# RP2040_MCU.net
KiCad netlist of a schematic drawn in Altium Designer
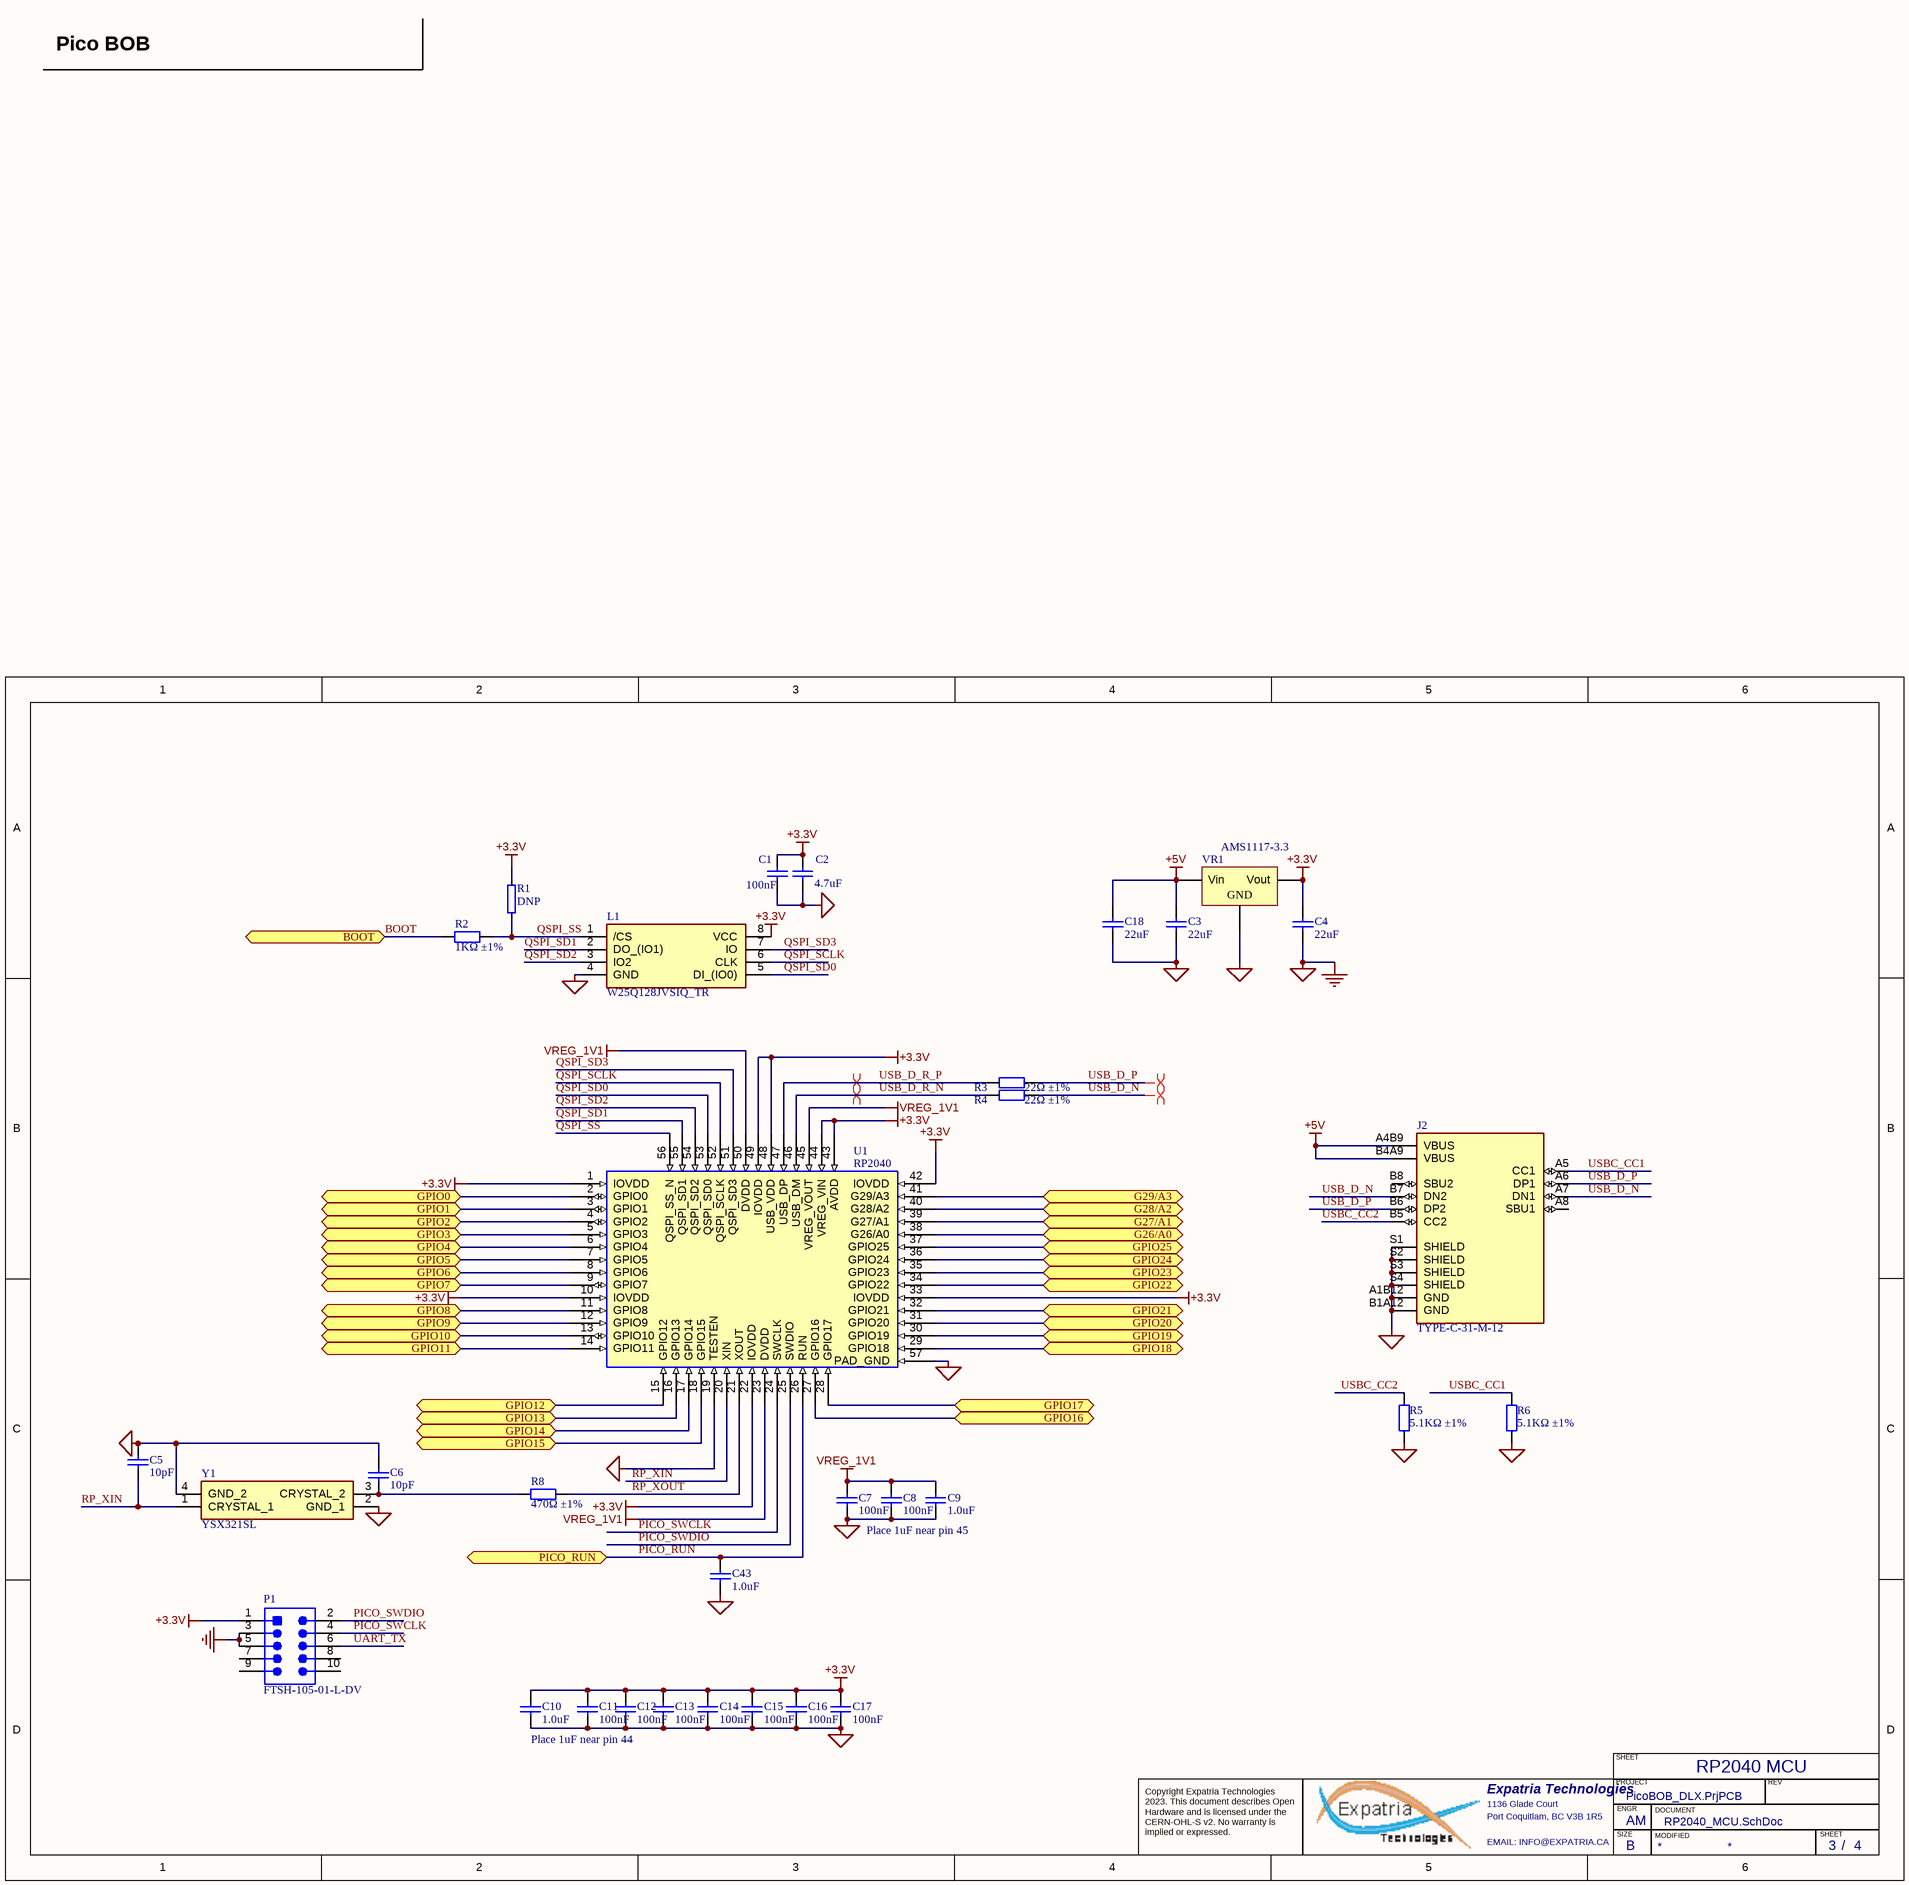
[diagram p0: RP2040_MCU.SchDoc]

(export (version "E")
  (design (tool "Eeschema 10.0.6"))
  (components
    (comp (ref "C1")
      (value "100nF")
      (footprint "0402_C")
      (description "Chip capacitors")
      (fields
        (field (name "MANUFACTURER") "Samsung Electro-Mechanics")
        (field (name "PARTNUMBER") "CL05B104KO5NNNC")
      )
      (libsource (lib "Cap") (part "0402 100nF (104) 10% 16V"))
    )
    (comp (ref "C2")
      (value "4.7uF")
      (footprint "0402_C")
      (description "Chip capacitor")
      (fields
        (field (name "MANUFACTURER") "Samsung Electro-Mechanics")
        (field (name "PARTNUMBER") "CL05A475MP5NRNC")
      )
      (libsource (lib "Cap") (part "0402 4.7uF (475) 20% 10V"))
    )
    (comp (ref "C3")
      (value "22uF")
      (footprint "0805_C")
      (description "Chip capacitors")
      (fields
        (field (name "MANUFACTURER") "Samsung Electro-Mechanics")
        (field (name "PARTNUMBER") "CL21A226MAQNNNE")
      )
      (libsource (lib "Cap") (part "0805 22uF (226) 20% 25V"))
    )
    (comp (ref "C4")
      (value "22uF")
      (footprint "0805_C")
      (description "Chip capacitors")
      (fields
        (field (name "MANUFACTURER") "Samsung Electro-Mechanics")
        (field (name "PARTNUMBER") "CL21A226MAQNNNE")
      )
      (libsource (lib "Cap") (part "0805 22uF (226) 20% 25V"))
    )
    (comp (ref "C5")
      (value "10pF")
      (footprint "0402_C")
      (description "Chip capacitors")
      (fields
        (field (name "MANUFACTURER") "Samsung Electro-Mechanics")
        (field (name "PARTNUMBER") "CL05C100JB5NNNC")
      )
      (libsource (lib "Cap") (part "0402 10pF (100) 5% 50V"))
    )
    (comp (ref "C6")
      (value "10pF")
      (footprint "0402_C")
      (description "Chip capacitors")
      (fields
        (field (name "MANUFACTURER") "Samsung Electro-Mechanics")
        (field (name "PARTNUMBER") "CL05C100JB5NNNC")
      )
      (libsource (lib "Cap") (part "0402 10pF (100) 5% 50V"))
    )
    (comp (ref "C7")
      (value "100nF")
      (footprint "0402_C")
      (description "Chip capacitors")
      (fields
        (field (name "MANUFACTURER") "Samsung Electro-Mechanics")
        (field (name "PARTNUMBER") "CL05B104KO5NNNC")
      )
      (libsource (lib "Cap") (part "0402 100nF (104) 10% 16V"))
    )
    (comp (ref "C8")
      (value "100nF")
      (footprint "0402_C")
      (description "Chip capacitors")
      (fields
        (field (name "MANUFACTURER") "Samsung Electro-Mechanics")
        (field (name "PARTNUMBER") "CL05B104KO5NNNC")
      )
      (libsource (lib "Cap") (part "0402 100nF (104) 10% 16V"))
    )
    (comp (ref "C9")
      (value "1.0uF")
      (footprint "0402_C")
      (description "Chip capacitor")
      (fields
        (field (name "MANUFACTURER") "Samsung Electro-Mechanics")
        (field (name "PARTNUMBER") "CL05A105KA5NQNC")
      )
      (libsource (lib "Cap") (part "0402 1.0uF (105) 10% 25V"))
    )
    (comp (ref "C10")
      (value "1.0uF")
      (footprint "0402_C")
      (description "Chip capacitor")
      (fields
        (field (name "MANUFACTURER") "Samsung Electro-Mechanics")
        (field (name "PARTNUMBER") "CL05A105KA5NQNC")
      )
      (libsource (lib "Cap") (part "0402 1.0uF (105) 10% 25V"))
    )
    (comp (ref "C11")
      (value "100nF")
      (footprint "0402_C")
      (description "Chip capacitors")
      (fields
        (field (name "MANUFACTURER") "Samsung Electro-Mechanics")
        (field (name "PARTNUMBER") "CL05B104KO5NNNC")
      )
      (libsource (lib "Cap") (part "0402 100nF (104) 10% 16V"))
    )
    (comp (ref "C12")
      (value "100nF")
      (footprint "0402_C")
      (description "Chip capacitors")
      (fields
        (field (name "MANUFACTURER") "Samsung Electro-Mechanics")
        (field (name "PARTNUMBER") "CL05B104KO5NNNC")
      )
      (libsource (lib "Cap") (part "0402 100nF (104) 10% 16V"))
    )
    (comp (ref "C13")
      (value "100nF")
      (footprint "0402_C")
      (description "Chip capacitors")
      (fields
        (field (name "MANUFACTURER") "Samsung Electro-Mechanics")
        (field (name "PARTNUMBER") "CL05B104KO5NNNC")
      )
      (libsource (lib "Cap") (part "0402 100nF (104) 10% 16V"))
    )
    (comp (ref "C14")
      (value "100nF")
      (footprint "0402_C")
      (description "Chip capacitors")
      (fields
        (field (name "MANUFACTURER") "Samsung Electro-Mechanics")
        (field (name "PARTNUMBER") "CL05B104KO5NNNC")
      )
      (libsource (lib "Cap") (part "0402 100nF (104) 10% 16V"))
    )
    (comp (ref "C15")
      (value "100nF")
      (footprint "0402_C")
      (description "Chip capacitors")
      (fields
        (field (name "MANUFACTURER") "Samsung Electro-Mechanics")
        (field (name "PARTNUMBER") "CL05B104KO5NNNC")
      )
      (libsource (lib "Cap") (part "0402 100nF (104) 10% 16V"))
    )
    (comp (ref "C16")
      (value "100nF")
      (footprint "0402_C")
      (description "Chip capacitors")
      (fields
        (field (name "MANUFACTURER") "Samsung Electro-Mechanics")
        (field (name "PARTNUMBER") "CL05B104KO5NNNC")
      )
      (libsource (lib "Cap") (part "0402 100nF (104) 10% 16V"))
    )
    (comp (ref "C17")
      (value "100nF")
      (footprint "0402_C")
      (description "Chip capacitors")
      (fields
        (field (name "MANUFACTURER") "Samsung Electro-Mechanics")
        (field (name "PARTNUMBER") "CL05B104KO5NNNC")
      )
      (libsource (lib "Cap") (part "0402 100nF (104) 10% 16V"))
    )
    (comp (ref "C18")
      (value "22uF")
      (footprint "0805_C")
      (description "Chip capacitors")
      (fields
        (field (name "MANUFACTURER") "Samsung Electro-Mechanics")
        (field (name "PARTNUMBER") "CL21A226MAQNNNE")
      )
      (libsource (lib "Cap") (part "0805 22uF (226) 20% 25V"))
    )
    (comp (ref "C43")
      (value "1.0uF")
      (footprint "0402_C")
      (description "Chip capacitor")
      (fields
        (field (name "MANUFACTURER") "Samsung Electro-Mechanics")
        (field (name "PARTNUMBER") "CL05A105KA5NQNC")
      )
      (libsource (lib "Cap") (part "0402 1.0uF (105) 10% 25V"))
    )
    (comp (ref "J2")
      (value "TYPE-C-31-M-12")
      (footprint "HRO_TYPE-C-31-M-12")
      (description "USB Connectors 24 Receptacle 1 8.94*7.3mm RoHS")
      (fields (field (name "MF") "HRO Electronics Co., Ltd."))
      (libsource (lib "Universal_CNC_Breakout") (part "TYPE-C-31-M-12"))
    )
    (comp (ref "L1")
      (value "W25Q128JVSIQ_TR")
      (footprint "SamacSys:SOIC127P780X195-8N")
      (description "Inductor")
      (fields
        (field (name "MANUFACTURER_PART_NUMBER") "W25Q128JVSIQ TR")
        (field (name "MOUSER PART NUMBER") "454-W25Q128JVSIQTR")
      )
      (libsource (lib "*") (part "W25Q128JVSIQ_TR"))
    )
    (comp (ref "P1")
      (value "FTSH-105-01-L-DV")
      (footprint "SMTC-FTSH-105-01-L-DV_V")
      (description "Male Header, Pitch 1.27 mm, 2 x 5 Position, Height 5.96 mm, -55 to 125 degC, RoHS, Bulk")
      (fields (field (name "MANUFACTURER") "Samtec"))
      (libsource (lib "Altium Content Vault") (part "CN-2P-M-R10"))
    )
    (comp (ref "R1")
      (value "DNP")
      (footprint "0402")
      (description "Resistor, ±5%, 0.05W")
      (fields (field (name "PART NUMBER") "R0201-0R") (field (name "PUBLISHER") "Nordic Semiconductor"))
      (libsource (lib "Passives") (part "RES"))
    )
    (comp (ref "R2")
      (value "1KΩ ±1%")
      (footprint "0402_R")
      (description "Chip resistor")
      (fields (field (name "MANUFACTURER") "Uniroyal Elec") (field (name "PARTNUMBER") "0402WGF1001TCE"))
      (libsource (lib "RES") (part "0402 1K (1001) 1%"))
    )
    (comp (ref "R3")
      (value "22Ω ±1%")
      (footprint "0402_R")
      (description "Chip resistor")
      (fields (field (name "MANUFACTURER") "Uniroyal Elec") (field (name "PARTNUMBER") "0402WGF220JTCE"))
      (libsource (lib "RES") (part "0402 22R (22R0) 1%"))
    )
    (comp (ref "R4")
      (value "22Ω ±1%")
      (footprint "0402_R")
      (description "Chip resistor")
      (fields (field (name "MANUFACTURER") "Uniroyal Elec") (field (name "PARTNUMBER") "0402WGF220JTCE"))
      (libsource (lib "RES") (part "0402 22R (22R0) 1%"))
    )
    (comp (ref "R5")
      (value "5.1KΩ ±1%")
      (footprint "0402_R")
      (description "Chip resistor")
      (fields (field (name "MANUFACTURER") "Uniroyal Elec") (field (name "PARTNUMBER") "0402WGF5101TCE"))
      (libsource (lib "RES") (part "0402 5.1K (5101) 1%"))
    )
    (comp (ref "R6")
      (value "5.1KΩ ±1%")
      (footprint "0402_R")
      (description "Chip resistor")
      (fields (field (name "MANUFACTURER") "Uniroyal Elec") (field (name "PARTNUMBER") "0402WGF5101TCE"))
      (libsource (lib "RES") (part "0402 5.1K (5101) 1%"))
    )
    (comp (ref "R8")
      (value "470Ω ±1%")
      (footprint "0402_R")
      (description "Chip resistor")
      (fields (field (name "MANUFACTURER") "Uniroyal Elec") (field (name "PARTNUMBER") "0402WGF4700TCE"))
      (libsource (lib "RES") (part "0402 470R (4700) 1%"))
    )
    (comp (ref "U1")
      (value "RP2040")
      (footprint "RP2040")
      (description "RP2040 First MCU from RPI")
      (libsource (lib "Universal_CNC_Breakout") (part "RP2040"))
    )
    (comp (ref "VR1")
      (value "AMS1117-3.3")
      (footprint "SOT-223")
      (description "Vout=3.3V 1A 72dB@(120Hz) (LDO)")
      (libsource (lib "LDO") (part "SOT-223 AMS1117-3.3"))
    )
    (comp (ref "Y1")
      (value "YSX321SL")
      (footprint "SamacSys:YSX321SL")
      (description "Crystal or Oscillator")
      (libsource (lib "*") (part "YSX321SL"))
    )
  )
  (nets
    (net (code "1") (name "+3.3V") (class "Default")
      (node (ref "C1") (pin "2") (pinfunction "2_2") (pintype "passive"))
      (node (ref "C10") (pin "2") (pinfunction "2_2") (pintype "passive"))
      (node (ref "C11") (pin "2") (pinfunction "2_2") (pintype "passive"))
      (node (ref "C12") (pin "2") (pinfunction "2_2") (pintype "passive"))
      (node (ref "C13") (pin "2") (pinfunction "2_2") (pintype "passive"))
      (node (ref "C14") (pin "2") (pinfunction "2_2") (pintype "passive"))
      (node (ref "C15") (pin "2") (pinfunction "2_2") (pintype "passive"))
      (node (ref "C16") (pin "2") (pinfunction "2_2") (pintype "passive"))
      (node (ref "C17") (pin "2") (pinfunction "2_2") (pintype "passive"))
      (node (ref "C2") (pin "2") (pinfunction "2_2") (pintype "passive"))
      (node (ref "C4") (pin "2") (pinfunction "2_2") (pintype "passive"))
      (node (ref "L1") (pin "8") (pinfunction "VCC_8") (pintype "passive"))
      (node (ref "P1") (pin "1") (pinfunction "1_1") (pintype "passive"))
      (node (ref "R1") (pin "2") (pinfunction "2_2") (pintype "passive"))
      (node (ref "U1") (pin "1") (pinfunction "IOVDD_1") (pintype "input"))
      (node (ref "U1") (pin "10") (pinfunction "IOVDD_10") (pintype "input"))
      (node (ref "U1") (pin "22") (pinfunction "IOVDD_22") (pintype "input"))
      (node (ref "U1") (pin "33") (pinfunction "IOVDD_33") (pintype "input"))
      (node (ref "U1") (pin "42") (pinfunction "IOVDD_42") (pintype "input"))
      (node (ref "U1") (pin "43") (pinfunction "AVDD_43") (pintype "input"))
      (node (ref "U1") (pin "44") (pinfunction "VREG_VIN_44") (pintype "input"))
      (node (ref "U1") (pin "48") (pinfunction "USB_VDD_48") (pintype "input"))
      (node (ref "U1") (pin "49") (pinfunction "IOVDD_49") (pintype "input"))
      (node (ref "VR1") (pin "2") (pinfunction "Vout_2") (pintype "passive"))
    )
    (net (code "2") (name "+5V") (class "Default")
      (node (ref "C18") (pin "2") (pinfunction "2_2") (pintype "passive"))
      (node (ref "C3") (pin "2") (pinfunction "2_2") (pintype "passive"))
      (node (ref "J2") (pin "A4B9") (pinfunction "VBUS_A4B9") (pintype "power_in"))
      (node (ref "J2") (pin "B4A9") (pinfunction "VBUS_B4A9") (pintype "power_in"))
      (node (ref "VR1") (pin "3") (pinfunction "Vin_3") (pintype "passive"))
    )
    (net (code "3") (name "/BOOT") (class "Default")
      (node (ref "R2") (pin "1") (pinfunction "1_1") (pintype "passive"))
    )
    (net (code "4") (name "/G26{slash}A0") (class "Default")
      (node (ref "U1") (pin "38") (pinfunction "G26/A0_38") (pintype "input"))
    )
    (net (code "5") (name "/G27{slash}A1") (class "Default")
      (node (ref "U1") (pin "39") (pinfunction "G27/A1_39") (pintype "input"))
    )
    (net (code "6") (name "/G28{slash}A2") (class "Default")
      (node (ref "U1") (pin "40") (pinfunction "G28/A2_40") (pintype "input"))
    )
    (net (code "7") (name "/G29{slash}A3") (class "Default")
      (node (ref "U1") (pin "41") (pinfunction "G29/A3_41") (pintype "input"))
    )
    (net (code "8") (name "/GPIO0") (class "Default")
      (node (ref "U1") (pin "2") (pinfunction "GPIO0_2") (pintype "bidirectional"))
    )
    (net (code "9") (name "/GPIO1") (class "Default")
      (node (ref "U1") (pin "3") (pinfunction "GPIO1_3") (pintype "bidirectional"))
    )
    (net (code "10") (name "/GPIO2") (class "Default")
      (node (ref "U1") (pin "4") (pinfunction "GPIO2_4") (pintype "bidirectional"))
    )
    (net (code "11") (name "/GPIO3") (class "Default")
      (node (ref "U1") (pin "5") (pinfunction "GPIO3_5") (pintype "input"))
    )
    (net (code "12") (name "/GPIO4") (class "Default")
      (node (ref "U1") (pin "6") (pinfunction "GPIO4_6") (pintype "input"))
    )
    (net (code "13") (name "/GPIO5") (class "Default")
      (node (ref "U1") (pin "7") (pinfunction "GPIO5_7") (pintype "input"))
    )
    (net (code "14") (name "/GPIO6") (class "Default")
      (node (ref "U1") (pin "8") (pinfunction "GPIO6_8") (pintype "input"))
    )
    (net (code "15") (name "/GPIO7") (class "Default")
      (node (ref "U1") (pin "9") (pinfunction "GPIO7_9") (pintype "bidirectional"))
    )
    (net (code "16") (name "/GPIO8") (class "Default")
      (node (ref "U1") (pin "11") (pinfunction "GPIO8_11") (pintype "input"))
    )
    (net (code "17") (name "/GPIO9") (class "Default")
      (node (ref "U1") (pin "12") (pinfunction "GPIO9_12") (pintype "input"))
    )
    (net (code "18") (name "/GPIO10") (class "Default")
      (node (ref "U1") (pin "13") (pinfunction "GPIO10_13") (pintype "bidirectional"))
    )
    (net (code "19") (name "/GPIO11") (class "Default")
      (node (ref "U1") (pin "14") (pinfunction "GPIO11_14") (pintype "input"))
    )
    (net (code "20") (name "/GPIO12") (class "Default")
      (node (ref "U1") (pin "15") (pinfunction "GPIO12_15") (pintype "input"))
    )
    (net (code "21") (name "/GPIO13") (class "Default")
      (node (ref "U1") (pin "16") (pinfunction "GPIO13_16") (pintype "input"))
    )
    (net (code "22") (name "/GPIO14") (class "Default")
      (node (ref "U1") (pin "17") (pinfunction "GPIO14_17") (pintype "input"))
    )
    (net (code "23") (name "/GPIO15") (class "Default")
      (node (ref "U1") (pin "18") (pinfunction "GPIO15_18") (pintype "input"))
    )
    (net (code "24") (name "/GPIO16") (class "Default")
      (node (ref "U1") (pin "27") (pinfunction "GPIO16_27") (pintype "input"))
    )
    (net (code "25") (name "/GPIO17") (class "Default")
      (node (ref "U1") (pin "28") (pinfunction "GPIO17_28") (pintype "input"))
    )
    (net (code "26") (name "/GPIO18") (class "Default")
      (node (ref "U1") (pin "29") (pinfunction "GPIO18_29") (pintype "input"))
    )
    (net (code "27") (name "/GPIO19") (class "Default")
      (node (ref "U1") (pin "30") (pinfunction "GPIO19_30") (pintype "input"))
    )
    (net (code "28") (name "/GPIO20") (class "Default")
      (node (ref "U1") (pin "31") (pinfunction "GPIO20_31") (pintype "input"))
    )
    (net (code "29") (name "/GPIO21") (class "Default")
      (node (ref "U1") (pin "32") (pinfunction "GPIO21_32") (pintype "input"))
    )
    (net (code "30") (name "/GPIO22") (class "Default")
      (node (ref "U1") (pin "34") (pinfunction "GPIO22_34") (pintype "input"))
    )
    (net (code "31") (name "/GPIO23") (class "Default")
      (node (ref "U1") (pin "35") (pinfunction "GPIO23_35") (pintype "input"))
    )
    (net (code "32") (name "/GPIO24") (class "Default")
      (node (ref "U1") (pin "36") (pinfunction "GPIO24_36") (pintype "input"))
    )
    (net (code "33") (name "/GPIO25") (class "Default")
      (node (ref "U1") (pin "37") (pinfunction "GPIO25_37") (pintype "input"))
    )
    (net (code "34") (name "/PICO_RUN") (class "Default")
      (node (ref "C43") (pin "2") (pinfunction "2_2") (pintype "passive"))
      (node (ref "U1") (pin "26") (pinfunction "RUN_26") (pintype "input"))
    )
    (net (code "35") (name "/PICO_SWCLK") (class "Default")
      (node (ref "P1") (pin "4") (pinfunction "4_4") (pintype "passive"))
      (node (ref "U1") (pin "24") (pinfunction "SWCLK_24") (pintype "input"))
    )
    (net (code "36") (name "/PICO_SWDIO") (class "Default")
      (node (ref "P1") (pin "2") (pinfunction "2_2") (pintype "passive"))
      (node (ref "U1") (pin "25") (pinfunction "SWDIO_25") (pintype "input"))
    )
    (net (code "37") (name "/QSPI_SCLK") (class "Default")
      (node (ref "L1") (pin "6") (pinfunction "CLK_6") (pintype "passive"))
      (node (ref "U1") (pin "52") (pinfunction "QSPI_SCLK_52") (pintype "input"))
    )
    (net (code "38") (name "/QSPI_SD0") (class "Default")
      (node (ref "L1") (pin "5") (pinfunction "DI_(IO0)_5") (pintype "passive"))
      (node (ref "U1") (pin "53") (pinfunction "QSPI_SD0_53") (pintype "input"))
    )
    (net (code "39") (name "/QSPI_SD1") (class "Default")
      (node (ref "L1") (pin "2") (pinfunction "DO_(IO1)_2") (pintype "passive"))
      (node (ref "U1") (pin "55") (pinfunction "QSPI_SD1_55") (pintype "input"))
    )
    (net (code "40") (name "/QSPI_SD2") (class "Default")
      (node (ref "L1") (pin "3") (pinfunction "IO2_3") (pintype "passive"))
      (node (ref "U1") (pin "54") (pinfunction "QSPI_SD2_54") (pintype "input"))
    )
    (net (code "41") (name "/QSPI_SD3") (class "Default")
      (node (ref "L1") (pin "7") (pinfunction "IO_7") (pintype "passive"))
      (node (ref "U1") (pin "51") (pinfunction "QSPI_SD3_51") (pintype "input"))
    )
    (net (code "42") (name "/QSPI_SS") (class "Default")
      (node (ref "L1") (pin "1") (pinfunction "/CS_1") (pintype "passive"))
      (node (ref "R1") (pin "1") (pinfunction "1_1") (pintype "passive"))
      (node (ref "R2") (pin "2") (pinfunction "2_2") (pintype "passive"))
      (node (ref "U1") (pin "56") (pinfunction "QSPI_SS_N_56") (pintype "input"))
    )
    (net (code "43") (name "/RP_XIN") (class "Default")
      (node (ref "C5") (pin "1") (pinfunction "1_1") (pintype "passive"))
      (node (ref "U1") (pin "20") (pinfunction "XIN_20") (pintype "input"))
      (node (ref "Y1") (pin "1") (pinfunction "CRYSTAL_1_1") (pintype "passive"))
    )
    (net (code "44") (name "/RP_XOUT") (class "Default")
      (node (ref "R8") (pin "2") (pinfunction "2_2") (pintype "passive"))
      (node (ref "U1") (pin "21") (pinfunction "XOUT_21") (pintype "input"))
    )
    (net (code "45") (name "/UART_TX") (class "Default")
      (node (ref "P1") (pin "6") (pinfunction "6_6") (pintype "passive"))
    )
    (net (code "46") (name "/USBC_CC1") (class "Default")
      (node (ref "J2") (pin "A5") (pinfunction "CC1_A5") (pintype "bidirectional"))
      (node (ref "R6") (pin "1") (pinfunction "1_1") (pintype "passive"))
    )
    (net (code "47") (name "/USBC_CC2") (class "Default")
      (node (ref "J2") (pin "B5") (pinfunction "CC2_B5") (pintype "bidirectional"))
      (node (ref "R5") (pin "1") (pinfunction "1_1") (pintype "passive"))
    )
    (net (code "48") (name "/USB_D_N") (class "Default")
      (node (ref "J2") (pin "A7") (pinfunction "DN1_A7") (pintype "bidirectional"))
      (node (ref "J2") (pin "B7") (pinfunction "DN2_B7") (pintype "bidirectional"))
      (node (ref "R4") (pin "1") (pinfunction "1_1") (pintype "passive"))
    )
    (net (code "49") (name "/USB_D_P") (class "Default")
      (node (ref "J2") (pin "A6") (pinfunction "DP1_A6") (pintype "bidirectional"))
      (node (ref "J2") (pin "B6") (pinfunction "DP2_B6") (pintype "bidirectional"))
      (node (ref "R3") (pin "1") (pinfunction "1_1") (pintype "passive"))
    )
    (net (code "50") (name "/USB_D_R_N") (class "Default")
      (node (ref "R4") (pin "2") (pinfunction "2_2") (pintype "passive"))
      (node (ref "U1") (pin "46") (pinfunction "USB_DM_46") (pintype "input"))
    )
    (net (code "51") (name "/USB_D_R_P") (class "Default")
      (node (ref "R3") (pin "2") (pinfunction "2_2") (pintype "passive"))
      (node (ref "U1") (pin "47") (pinfunction "USB_DP_47") (pintype "input"))
    )
    (net (code "52") (name "GND") (class "Default")
      (node (ref "C1") (pin "1") (pinfunction "1_1") (pintype "passive"))
      (node (ref "C10") (pin "1") (pinfunction "1_1") (pintype "passive"))
      (node (ref "C11") (pin "1") (pinfunction "1_1") (pintype "passive"))
      (node (ref "C12") (pin "1") (pinfunction "1_1") (pintype "passive"))
      (node (ref "C13") (pin "1") (pinfunction "1_1") (pintype "passive"))
      (node (ref "C14") (pin "1") (pinfunction "1_1") (pintype "passive"))
      (node (ref "C15") (pin "1") (pinfunction "1_1") (pintype "passive"))
      (node (ref "C16") (pin "1") (pinfunction "1_1") (pintype "passive"))
      (node (ref "C17") (pin "1") (pinfunction "1_1") (pintype "passive"))
      (node (ref "C18") (pin "1") (pinfunction "1_1") (pintype "passive"))
      (node (ref "C2") (pin "1") (pinfunction "1_1") (pintype "passive"))
      (node (ref "C3") (pin "1") (pinfunction "1_1") (pintype "passive"))
      (node (ref "C4") (pin "1") (pinfunction "1_1") (pintype "passive"))
      (node (ref "C43") (pin "1") (pinfunction "1_1") (pintype "passive"))
      (node (ref "C5") (pin "2") (pinfunction "2_2") (pintype "passive"))
      (node (ref "C6") (pin "2") (pinfunction "2_2") (pintype "passive"))
      (node (ref "C7") (pin "1") (pinfunction "1_1") (pintype "passive"))
      (node (ref "C8") (pin "1") (pinfunction "1_1") (pintype "passive"))
      (node (ref "C9") (pin "1") (pinfunction "1_1") (pintype "passive"))
      (node (ref "J2") (pin "A1B12") (pinfunction "GND_A1B12") (pintype "power_in"))
      (node (ref "J2") (pin "B1A12") (pinfunction "GND_B1A12") (pintype "power_in"))
      (node (ref "J2") (pin "S1") (pinfunction "SHIELD_S1") (pintype "passive"))
      (node (ref "J2") (pin "S2") (pinfunction "SHIELD_S2") (pintype "passive"))
      (node (ref "J2") (pin "S3") (pinfunction "SHIELD_S3") (pintype "passive"))
      (node (ref "J2") (pin "S4") (pinfunction "SHIELD_S4") (pintype "passive"))
      (node (ref "L1") (pin "4") (pinfunction "GND_4") (pintype "passive"))
      (node (ref "P1") (pin "3") (pinfunction "3_3") (pintype "passive"))
      (node (ref "P1") (pin "5") (pinfunction "5_5") (pintype "passive"))
      (node (ref "R5") (pin "2") (pinfunction "2_2") (pintype "passive"))
      (node (ref "R6") (pin "2") (pinfunction "2_2") (pintype "passive"))
      (node (ref "U1") (pin "19") (pinfunction "TESTEN_19") (pintype "input"))
      (node (ref "U1") (pin "57") (pinfunction "PAD_GND_57") (pintype "input"))
      (node (ref "VR1") (pin "1") (pinfunction "GND_1") (pintype "passive"))
      (node (ref "Y1") (pin "2") (pinfunction "GND_1_2") (pintype "passive"))
      (node (ref "Y1") (pin "4") (pinfunction "GND_2_4") (pintype "passive"))
    )
    (net (code "53") (name "Net-(Y1-CRYSTAL_2)") (class "Default")
      (node (ref "C6") (pin "1") (pinfunction "1_1") (pintype "passive"))
      (node (ref "R8") (pin "1") (pinfunction "1_1") (pintype "passive"))
      (node (ref "Y1") (pin "3") (pinfunction "CRYSTAL_2_3") (pintype "passive"))
    )
    (net (code "54") (name "VREG_1V1") (class "Default")
      (node (ref "C7") (pin "2") (pinfunction "2_2") (pintype "passive"))
      (node (ref "C8") (pin "2") (pinfunction "2_2") (pintype "passive"))
      (node (ref "C9") (pin "2") (pinfunction "2_2") (pintype "passive"))
      (node (ref "U1") (pin "23") (pinfunction "DVDD_23") (pintype "input"))
      (node (ref "U1") (pin "45") (pinfunction "VREG_VOUT_45") (pintype "input"))
      (node (ref "U1") (pin "50") (pinfunction "DVDD_50") (pintype "input"))
    )
    (net (code "55") (name "unconnected-(J2-SBU1-PadA8)") (class "Default")
      (node (ref "J2") (pin "A8") (pinfunction "SBU1_A8") (pintype "bidirectional"))
    )
    (net (code "56") (name "unconnected-(J2-SBU2-PadB8)") (class "Default")
      (node (ref "J2") (pin "B8") (pinfunction "SBU2_B8") (pintype "bidirectional"))
    )
    (net (code "57") (name "unconnected-(P1-Pad7)") (class "Default")
      (node (ref "P1") (pin "7") (pinfunction "7_7") (pintype "passive"))
    )
    (net (code "58") (name "unconnected-(P1-Pad8)") (class "Default")
      (node (ref "P1") (pin "8") (pinfunction "8_8") (pintype "passive"))
    )
    (net (code "59") (name "unconnected-(P1-Pad9)") (class "Default")
      (node (ref "P1") (pin "9") (pinfunction "9_9") (pintype "passive"))
    )
    (net (code "60") (name "unconnected-(P1-Pad10)") (class "Default")
      (node (ref "P1") (pin "10") (pinfunction "10_10") (pintype "passive"))
    )
  )
)
